# micro_amp_dual_buff.net
KiCad netlist of a schematic drawn in EAGLE
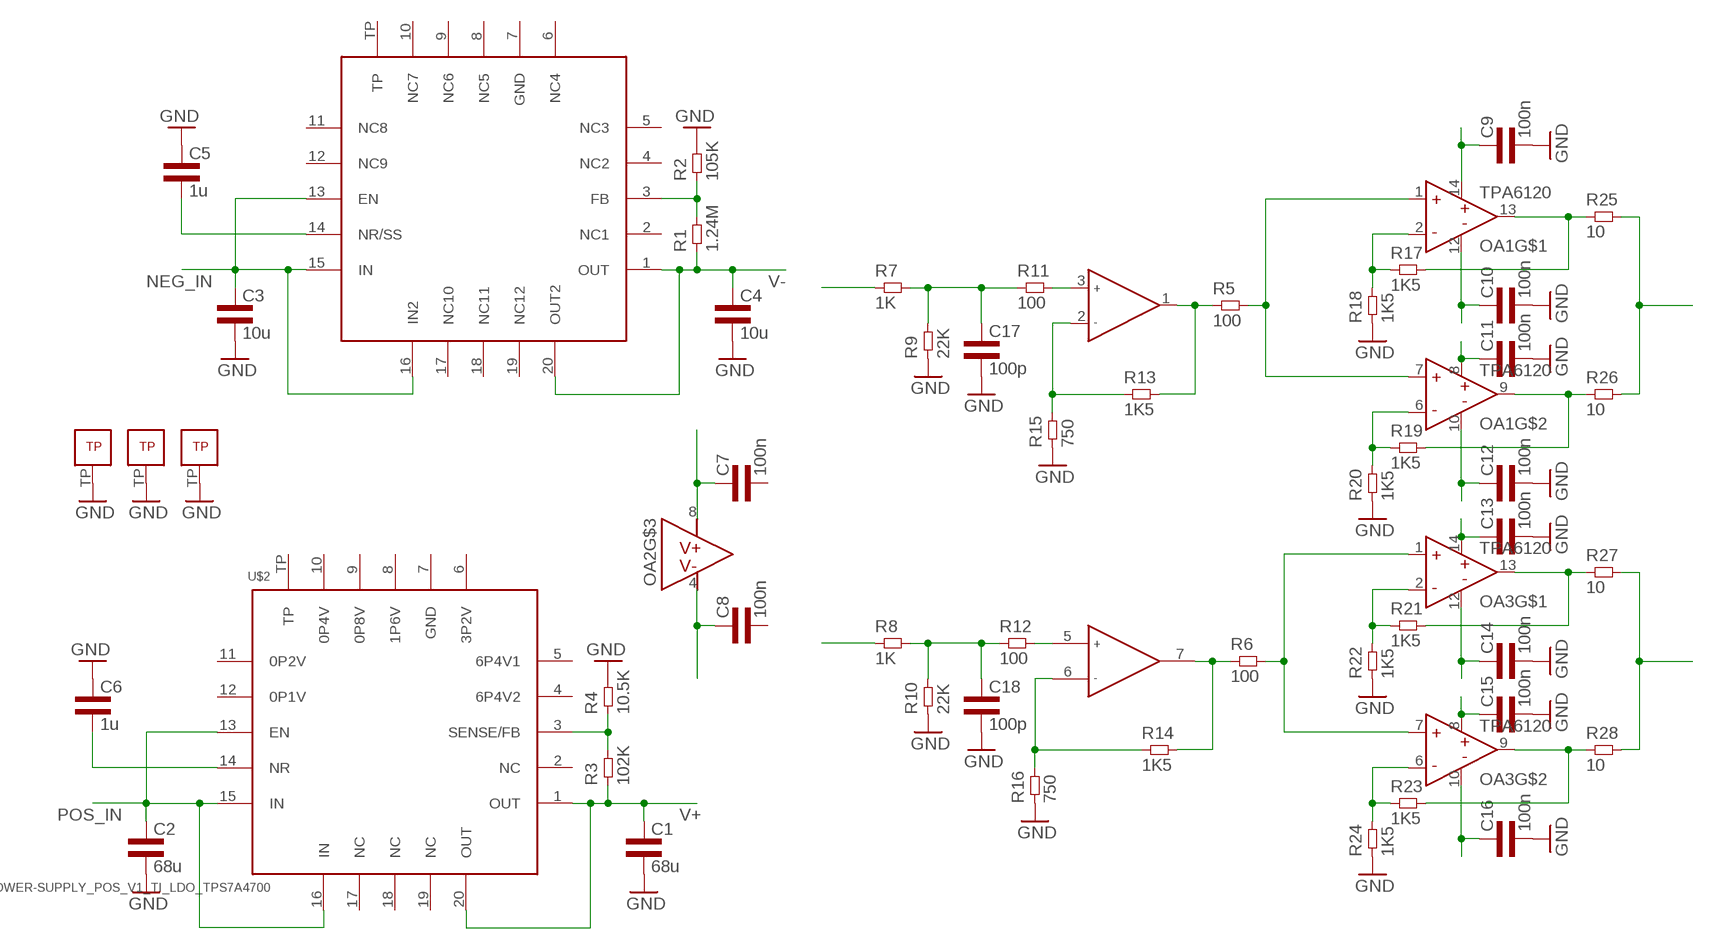
[diagram p0: schematic, sheet 1]

(export (version "E")
  (design (tool "Eeschema 10.0.6"))
  (components
    (comp (ref "C1")
      (value "68u")
      (footprint "eagle-import:1210L3")
      (libsource (lib "eagle-import") (part "CAP1210L3"))
    )
    (comp (ref "C2")
      (value "68u")
      (footprint "eagle-import:1210L3")
      (libsource (lib "eagle-import") (part "CAP1210L3"))
    )
    (comp (ref "C3")
      (value "10u")
      (footprint "eagle-import:0805L3")
      (libsource (lib "eagle-import") (part "CAP0805L3"))
    )
    (comp (ref "C4")
      (value "10u")
      (footprint "eagle-import:0805L3")
      (libsource (lib "eagle-import") (part "CAP0805L3"))
    )
    (comp (ref "C5")
      (value "1u")
      (footprint "eagle-import:0603L3")
      (libsource (lib "eagle-import") (part "CAP0603L3"))
    )
    (comp (ref "C6")
      (value "1u")
      (footprint "eagle-import:0603L3")
      (libsource (lib "eagle-import") (part "CAP0603L3"))
    )
    (comp (ref "C7")
      (value "100n")
      (footprint "eagle-import:0402L3")
      (libsource (lib "eagle-import") (part "CAP0402L3"))
    )
    (comp (ref "C8")
      (value "100n")
      (footprint "eagle-import:0402L3")
      (libsource (lib "eagle-import") (part "CAP0402L3"))
    )
    (comp (ref "C9")
      (value "100n")
      (footprint "eagle-import:0402L3")
      (libsource (lib "eagle-import") (part "CAP0402L3"))
    )
    (comp (ref "C10")
      (value "100n")
      (footprint "eagle-import:0402L3")
      (libsource (lib "eagle-import") (part "CAP0402L3"))
    )
    (comp (ref "C11")
      (value "100n")
      (footprint "eagle-import:0402L3")
      (libsource (lib "eagle-import") (part "CAP0402L3"))
    )
    (comp (ref "C12")
      (value "100n")
      (footprint "eagle-import:0402L3")
      (libsource (lib "eagle-import") (part "CAP0402L3"))
    )
    (comp (ref "C13")
      (value "100n")
      (footprint "eagle-import:0402L3")
      (libsource (lib "eagle-import") (part "CAP0402L3"))
    )
    (comp (ref "C14")
      (value "100n")
      (footprint "eagle-import:0402L3")
      (libsource (lib "eagle-import") (part "CAP0402L3"))
    )
    (comp (ref "C15")
      (value "100n")
      (footprint "eagle-import:0402L3")
      (libsource (lib "eagle-import") (part "CAP0402L3"))
    )
    (comp (ref "C16")
      (value "100n")
      (footprint "eagle-import:0402L3")
      (libsource (lib "eagle-import") (part "CAP0402L3"))
    )
    (comp (ref "C17")
      (value "100p")
      (footprint "eagle-import:0402L3")
      (libsource (lib "eagle-import") (part "CAP0402L3"))
    )
    (comp (ref "C18")
      (value "100p")
      (footprint "eagle-import:0402L3")
      (libsource (lib "eagle-import") (part "CAP0402L3"))
    )
    (comp (ref "OA1")
      (value "TPA6120QFN")
      (footprint "eagle-import:S-PVQFN-N14")
      (libsource (lib "eagle-import") (part "TPA6120QFN"))
    )
    (comp (ref "OA2")
      (value "OPA1612")
      (footprint "eagle-import:S-PWSON-N8")
      (libsource (lib "eagle-import") (part "OPA1612"))
    )
    (comp (ref "OA3")
      (value "TPA6120QFN")
      (footprint "eagle-import:S-PVQFN-N14")
      (libsource (lib "eagle-import") (part "TPA6120QFN"))
    )
    (comp (ref "R1")
      (value "1.24M")
      (footprint "eagle-import:0402L3")
      (libsource (lib "eagle-import") (part "RES0402L3"))
    )
    (comp (ref "R2")
      (value "105K")
      (footprint "eagle-import:0402L3")
      (libsource (lib "eagle-import") (part "RES0402L3"))
    )
    (comp (ref "R3")
      (value "102K")
      (footprint "eagle-import:0402L3")
      (libsource (lib "eagle-import") (part "RES0402L3"))
    )
    (comp (ref "R4")
      (value "10.5K")
      (footprint "eagle-import:0402L3")
      (libsource (lib "eagle-import") (part "RES0402L3"))
    )
    (comp (ref "R5")
      (value "100")
      (footprint "eagle-import:0402L3")
      (libsource (lib "eagle-import") (part "RES0402L3"))
    )
    (comp (ref "R6")
      (value "100")
      (footprint "eagle-import:0402L3")
      (libsource (lib "eagle-import") (part "RES0402L3"))
    )
    (comp (ref "R7")
      (value "1K")
      (footprint "eagle-import:0402L3")
      (libsource (lib "eagle-import") (part "RES0402L3"))
    )
    (comp (ref "R8")
      (value "1K")
      (footprint "eagle-import:0402L3")
      (libsource (lib "eagle-import") (part "RES0402L3"))
    )
    (comp (ref "R9")
      (value "22K")
      (footprint "eagle-import:0402L3")
      (libsource (lib "eagle-import") (part "RES0402L3"))
    )
    (comp (ref "R10")
      (value "22K")
      (footprint "eagle-import:0402L3")
      (libsource (lib "eagle-import") (part "RES0402L3"))
    )
    (comp (ref "R11")
      (value "100")
      (footprint "eagle-import:0402L3")
      (libsource (lib "eagle-import") (part "RES0402L3"))
    )
    (comp (ref "R12")
      (value "100")
      (footprint "eagle-import:0402L3")
      (libsource (lib "eagle-import") (part "RES0402L3"))
    )
    (comp (ref "R13")
      (value "1K5")
      (footprint "eagle-import:0402L3")
      (libsource (lib "eagle-import") (part "RES0402L3"))
    )
    (comp (ref "R14")
      (value "1K5")
      (footprint "eagle-import:0402L3")
      (libsource (lib "eagle-import") (part "RES0402L3"))
    )
    (comp (ref "R15")
      (value "750")
      (footprint "eagle-import:0402L3")
      (libsource (lib "eagle-import") (part "RES0402L3"))
    )
    (comp (ref "R16")
      (value "750")
      (footprint "eagle-import:0402L3")
      (libsource (lib "eagle-import") (part "RES0402L3"))
    )
    (comp (ref "R17")
      (value "1K5")
      (footprint "eagle-import:0402L3")
      (libsource (lib "eagle-import") (part "RES0402L3"))
    )
    (comp (ref "R18")
      (value "1K5")
      (footprint "eagle-import:0402L3")
      (libsource (lib "eagle-import") (part "RES0402L3"))
    )
    (comp (ref "R19")
      (value "1K5")
      (footprint "eagle-import:0402L3")
      (libsource (lib "eagle-import") (part "RES0402L3"))
    )
    (comp (ref "R20")
      (value "1K5")
      (footprint "eagle-import:0402L3")
      (libsource (lib "eagle-import") (part "RES0402L3"))
    )
    (comp (ref "R21")
      (value "1K5")
      (footprint "eagle-import:0402L3")
      (libsource (lib "eagle-import") (part "RES0402L3"))
    )
    (comp (ref "R22")
      (value "1K5")
      (footprint "eagle-import:0402L3")
      (libsource (lib "eagle-import") (part "RES0402L3"))
    )
    (comp (ref "R23")
      (value "1K5")
      (footprint "eagle-import:0402L3")
      (libsource (lib "eagle-import") (part "RES0402L3"))
    )
    (comp (ref "R24")
      (value "1K5")
      (footprint "eagle-import:0402L3")
      (libsource (lib "eagle-import") (part "RES0402L3"))
    )
    (comp (ref "R25")
      (value "10")
      (footprint "eagle-import:0805L3")
      (libsource (lib "eagle-import") (part "RES0805L3"))
    )
    (comp (ref "R26")
      (value "10")
      (footprint "eagle-import:0805L3")
      (libsource (lib "eagle-import") (part "RES0805L3"))
    )
    (comp (ref "R27")
      (value "10")
      (footprint "eagle-import:0805L3")
      (libsource (lib "eagle-import") (part "RES0805L3"))
    )
    (comp (ref "R28")
      (value "10")
      (footprint "eagle-import:0805L3")
      (libsource (lib "eagle-import") (part "RES0805L3"))
    )
    (comp (ref "U$1")
      (value "POWER-SUPPLY_POS_V1_TI_LDO_TPS7A3301RGWT")
      (footprint "eagle-import:POWER-SUPPLY_POS_V1_TI_LDO_VQFN-20")
      (libsource (lib "eagle-import") (part "POWER-SUPPLY_POS_V1_TI_LDO_TPS7A3301RGWT"))
    )
    (comp (ref "U$2")
      (value "POWER-SUPPLY_POS_V1_TI_LDO_TPS7A4700")
      (footprint "eagle-import:POWER-SUPPLY_POS_V1_TI_LDO_VQFN-20")
      (libsource (lib "eagle-import") (part "POWER-SUPPLY_POS_V1_TI_LDO_TPS7A4700"))
    )
  )
  (nets
    (net (code "1") (name "/NEG_IN") (class "Default")
      (node (ref "C3") (pin "1") (pinfunction "1_1") (pintype "bidirectional"))
      (node (ref "U$1") (pin "13") (pinfunction "EN_13") (pintype "bidirectional"))
      (node (ref "U$1") (pin "15") (pinfunction "IN_15") (pintype "bidirectional"))
      (node (ref "U$1") (pin "16") (pinfunction "IN2_16") (pintype "bidirectional"))
    )
    (net (code "2") (name "/POS_IN") (class "Default")
      (node (ref "C2") (pin "P$1") (pinfunction "1_P$1") (pintype "bidirectional"))
      (node (ref "U$2") (pin "13") (pinfunction "EN_13") (pintype "bidirectional"))
      (node (ref "U$2") (pin "15") (pinfunction "IN_15") (pintype "bidirectional"))
      (node (ref "U$2") (pin "16") (pinfunction "IN_16") (pintype "bidirectional"))
    )
    (net (code "3") (name "/V+") (class "Default")
      (node (ref "C1") (pin "P$1") (pinfunction "1_P$1") (pintype "bidirectional"))
      (node (ref "C11") (pin "P$1") (pinfunction "1_P$1") (pintype "bidirectional"))
      (node (ref "C13") (pin "P$1") (pinfunction "1_P$1") (pintype "bidirectional"))
      (node (ref "C15") (pin "P$1") (pinfunction "1_P$1") (pintype "bidirectional"))
      (node (ref "C7") (pin "P$1") (pinfunction "1_P$1") (pintype "bidirectional"))
      (node (ref "C9") (pin "P$1") (pinfunction "1_P$1") (pintype "bidirectional"))
      (node (ref "OA1") (pin "14") (pinfunction "V+_14") (pintype "bidirectional"))
      (node (ref "OA1") (pin "8") (pinfunction "V+_8") (pintype "bidirectional"))
      (node (ref "OA2") (pin "8") (pinfunction "V+_8") (pintype "power_in"))
      (node (ref "OA3") (pin "14") (pinfunction "V+_14") (pintype "bidirectional"))
      (node (ref "OA3") (pin "8") (pinfunction "V+_8") (pintype "bidirectional"))
      (node (ref "R3") (pin "P$1") (pinfunction "1_P$1") (pintype "bidirectional"))
      (node (ref "U$2") (pin "1") (pinfunction "OUT_1") (pintype "bidirectional"))
      (node (ref "U$2") (pin "20") (pinfunction "OUT_20") (pintype "bidirectional"))
    )
    (net (code "4") (name "/V-") (class "Default")
      (node (ref "C10") (pin "P$1") (pinfunction "1_P$1") (pintype "bidirectional"))
      (node (ref "C12") (pin "P$1") (pinfunction "1_P$1") (pintype "bidirectional"))
      (node (ref "C14") (pin "P$1") (pinfunction "1_P$1") (pintype "bidirectional"))
      (node (ref "C16") (pin "P$1") (pinfunction "1_P$1") (pintype "bidirectional"))
      (node (ref "C4") (pin "1") (pinfunction "1_1") (pintype "bidirectional"))
      (node (ref "C8") (pin "P$1") (pinfunction "1_P$1") (pintype "bidirectional"))
      (node (ref "OA1") (pin "10") (pinfunction "V-_10") (pintype "bidirectional"))
      (node (ref "OA1") (pin "12") (pinfunction "V-_12") (pintype "bidirectional"))
      (node (ref "OA2") (pin "4") (pinfunction "V-_4") (pintype "power_in"))
      (node (ref "OA3") (pin "10") (pinfunction "V-_10") (pintype "bidirectional"))
      (node (ref "OA3") (pin "12") (pinfunction "V-_12") (pintype "bidirectional"))
      (node (ref "R1") (pin "P$1") (pinfunction "1_P$1") (pintype "bidirectional"))
      (node (ref "U$1") (pin "1") (pinfunction "OUT_1") (pintype "bidirectional"))
      (node (ref "U$1") (pin "20") (pinfunction "OUT2_20") (pintype "bidirectional"))
    )
    (net (code "5") (name "GND") (class "Default")
      (node (ref "C1") (pin "P$2") (pinfunction "2_P$2") (pintype "bidirectional"))
      (node (ref "C10") (pin "P$2") (pinfunction "2_P$2") (pintype "bidirectional"))
      (node (ref "C11") (pin "P$2") (pinfunction "2_P$2") (pintype "bidirectional"))
      (node (ref "C12") (pin "P$2") (pinfunction "2_P$2") (pintype "bidirectional"))
      (node (ref "C13") (pin "P$2") (pinfunction "2_P$2") (pintype "bidirectional"))
      (node (ref "C14") (pin "P$2") (pinfunction "2_P$2") (pintype "bidirectional"))
      (node (ref "C15") (pin "P$2") (pinfunction "2_P$2") (pintype "bidirectional"))
      (node (ref "C16") (pin "P$2") (pinfunction "2_P$2") (pintype "bidirectional"))
      (node (ref "C17") (pin "P$2") (pinfunction "2_P$2") (pintype "bidirectional"))
      (node (ref "C18") (pin "P$2") (pinfunction "2_P$2") (pintype "bidirectional"))
      (node (ref "C2") (pin "P$2") (pinfunction "2_P$2") (pintype "bidirectional"))
      (node (ref "C3") (pin "2") (pinfunction "2_2") (pintype "bidirectional"))
      (node (ref "C4") (pin "2") (pinfunction "2_2") (pintype "bidirectional"))
      (node (ref "C5") (pin "P$1") (pinfunction "1_P$1") (pintype "bidirectional"))
      (node (ref "C6") (pin "P$1") (pinfunction "1_P$1") (pintype "bidirectional"))
      (node (ref "C9") (pin "P$2") (pinfunction "2_P$2") (pintype "bidirectional"))
      (node (ref "OA1") (pin "TP") (pinfunction "TP_TP") (pintype "bidirectional"))
      (node (ref "OA2") (pin "TP") (pinfunction "TP_TP") (pintype "bidirectional"))
      (node (ref "OA3") (pin "TP") (pinfunction "TP_TP") (pintype "bidirectional"))
      (node (ref "R10") (pin "P$1") (pinfunction "1_P$1") (pintype "bidirectional"))
      (node (ref "R15") (pin "P$1") (pinfunction "1_P$1") (pintype "bidirectional"))
      (node (ref "R16") (pin "P$1") (pinfunction "1_P$1") (pintype "bidirectional"))
      (node (ref "R18") (pin "P$1") (pinfunction "1_P$1") (pintype "bidirectional"))
      (node (ref "R2") (pin "P$2") (pinfunction "2_P$2") (pintype "bidirectional"))
      (node (ref "R20") (pin "P$1") (pinfunction "1_P$1") (pintype "bidirectional"))
      (node (ref "R22") (pin "P$1") (pinfunction "1_P$1") (pintype "bidirectional"))
      (node (ref "R24") (pin "P$1") (pinfunction "1_P$1") (pintype "bidirectional"))
      (node (ref "R4") (pin "P$2") (pinfunction "2_P$2") (pintype "bidirectional"))
      (node (ref "R9") (pin "P$1") (pinfunction "1_P$1") (pintype "bidirectional"))
    )
    (net (code "6") (name "Net-(C5-2)") (class "Default")
      (node (ref "C5") (pin "P$2") (pinfunction "2_P$2") (pintype "bidirectional"))
      (node (ref "U$1") (pin "14") (pinfunction "NR/SS_14") (pintype "bidirectional"))
    )
    (net (code "7") (name "Net-(C6-2)") (class "Default")
      (node (ref "C6") (pin "P$2") (pinfunction "2_P$2") (pintype "bidirectional"))
      (node (ref "U$2") (pin "14") (pinfunction "NR_14") (pintype "bidirectional"))
    )
    (net (code "8") (name "Net-(C17-1)") (class "Default")
      (node (ref "C17") (pin "P$1") (pinfunction "1_P$1") (pintype "bidirectional"))
      (node (ref "R11") (pin "P$1") (pinfunction "1_P$1") (pintype "bidirectional"))
      (node (ref "R7") (pin "P$2") (pinfunction "2_P$2") (pintype "bidirectional"))
      (node (ref "R9") (pin "P$2") (pinfunction "2_P$2") (pintype "bidirectional"))
    )
    (net (code "9") (name "Net-(C18-1)") (class "Default")
      (node (ref "C18") (pin "P$1") (pinfunction "1_P$1") (pintype "bidirectional"))
      (node (ref "R10") (pin "P$2") (pinfunction "2_P$2") (pintype "bidirectional"))
      (node (ref "R12") (pin "P$1") (pinfunction "1_P$1") (pintype "bidirectional"))
      (node (ref "R8") (pin "P$2") (pinfunction "2_P$2") (pintype "bidirectional"))
    )
    (net (code "10") (name "Net-(OA1A-IN+)") (class "Default")
      (node (ref "OA1") (pin "1") (pinfunction "IN+_1") (pintype "bidirectional"))
      (node (ref "OA1") (pin "7") (pinfunction "IN+_7") (pintype "bidirectional"))
      (node (ref "R5") (pin "P$2") (pinfunction "2_P$2") (pintype "bidirectional"))
    )
    (net (code "11") (name "Net-(OA1A-IN-)") (class "Default")
      (node (ref "OA1") (pin "2") (pinfunction "IN-_2") (pintype "bidirectional"))
      (node (ref "R17") (pin "P$1") (pinfunction "1_P$1") (pintype "bidirectional"))
      (node (ref "R18") (pin "P$2") (pinfunction "2_P$2") (pintype "bidirectional"))
    )
    (net (code "12") (name "Net-(OA1A-OUT)") (class "Default")
      (node (ref "OA1") (pin "13") (pinfunction "OUT_13") (pintype "bidirectional"))
      (node (ref "R17") (pin "P$2") (pinfunction "2_P$2") (pintype "bidirectional"))
      (node (ref "R25") (pin "1") (pinfunction "1_1") (pintype "bidirectional"))
    )
    (net (code "13") (name "Net-(OA1B-IN-)") (class "Default")
      (node (ref "OA1") (pin "6") (pinfunction "IN-_6") (pintype "bidirectional"))
      (node (ref "R19") (pin "P$1") (pinfunction "1_P$1") (pintype "bidirectional"))
      (node (ref "R20") (pin "P$2") (pinfunction "2_P$2") (pintype "bidirectional"))
    )
    (net (code "14") (name "Net-(OA1B-OUT)") (class "Default")
      (node (ref "OA1") (pin "9") (pinfunction "OUT_9") (pintype "bidirectional"))
      (node (ref "R19") (pin "P$2") (pinfunction "2_P$2") (pintype "bidirectional"))
      (node (ref "R26") (pin "1") (pinfunction "1_1") (pintype "bidirectional"))
    )
    (net (code "15") (name "Net-(OA2A-INA+)") (class "Default")
      (node (ref "OA2") (pin "3") (pinfunction "INA+_3") (pintype "bidirectional"))
      (node (ref "R11") (pin "P$2") (pinfunction "2_P$2") (pintype "bidirectional"))
    )
    (net (code "16") (name "Net-(OA2A-INA-)") (class "Default")
      (node (ref "OA2") (pin "2") (pinfunction "INA-_2") (pintype "bidirectional"))
      (node (ref "R13") (pin "P$1") (pinfunction "1_P$1") (pintype "bidirectional"))
      (node (ref "R15") (pin "P$2") (pinfunction "2_P$2") (pintype "bidirectional"))
    )
    (net (code "17") (name "Net-(OA2A-OUTA)") (class "Default")
      (node (ref "OA2") (pin "1") (pinfunction "OUTA_1") (pintype "bidirectional"))
      (node (ref "R13") (pin "P$2") (pinfunction "2_P$2") (pintype "bidirectional"))
      (node (ref "R5") (pin "P$1") (pinfunction "1_P$1") (pintype "bidirectional"))
    )
    (net (code "18") (name "Net-(OA2B-INB+)") (class "Default")
      (node (ref "OA2") (pin "5") (pinfunction "INB+_5") (pintype "bidirectional"))
      (node (ref "R12") (pin "P$2") (pinfunction "2_P$2") (pintype "bidirectional"))
    )
    (net (code "19") (name "Net-(OA2B-INB-)") (class "Default")
      (node (ref "OA2") (pin "6") (pinfunction "INB-_6") (pintype "bidirectional"))
      (node (ref "R14") (pin "P$1") (pinfunction "1_P$1") (pintype "bidirectional"))
      (node (ref "R16") (pin "P$2") (pinfunction "2_P$2") (pintype "bidirectional"))
    )
    (net (code "20") (name "Net-(OA2B-OUTB)") (class "Default")
      (node (ref "OA2") (pin "7") (pinfunction "OUTB_7") (pintype "bidirectional"))
      (node (ref "R14") (pin "P$2") (pinfunction "2_P$2") (pintype "bidirectional"))
      (node (ref "R6") (pin "P$1") (pinfunction "1_P$1") (pintype "bidirectional"))
    )
    (net (code "21") (name "Net-(OA3A-IN+)") (class "Default")
      (node (ref "OA3") (pin "1") (pinfunction "IN+_1") (pintype "bidirectional"))
      (node (ref "OA3") (pin "7") (pinfunction "IN+_7") (pintype "bidirectional"))
      (node (ref "R6") (pin "P$2") (pinfunction "2_P$2") (pintype "bidirectional"))
    )
    (net (code "22") (name "Net-(OA3A-IN-)") (class "Default")
      (node (ref "OA3") (pin "2") (pinfunction "IN-_2") (pintype "bidirectional"))
      (node (ref "R21") (pin "P$1") (pinfunction "1_P$1") (pintype "bidirectional"))
      (node (ref "R22") (pin "P$2") (pinfunction "2_P$2") (pintype "bidirectional"))
    )
    (net (code "23") (name "Net-(OA3A-OUT)") (class "Default")
      (node (ref "OA3") (pin "13") (pinfunction "OUT_13") (pintype "bidirectional"))
      (node (ref "R21") (pin "P$2") (pinfunction "2_P$2") (pintype "bidirectional"))
      (node (ref "R27") (pin "1") (pinfunction "1_1") (pintype "bidirectional"))
    )
    (net (code "24") (name "Net-(OA3B-IN-)") (class "Default")
      (node (ref "OA3") (pin "6") (pinfunction "IN-_6") (pintype "bidirectional"))
      (node (ref "R23") (pin "P$1") (pinfunction "1_P$1") (pintype "bidirectional"))
      (node (ref "R24") (pin "P$2") (pinfunction "2_P$2") (pintype "bidirectional"))
    )
    (net (code "25") (name "Net-(OA3B-OUT)") (class "Default")
      (node (ref "OA3") (pin "9") (pinfunction "OUT_9") (pintype "bidirectional"))
      (node (ref "R23") (pin "P$2") (pinfunction "2_P$2") (pintype "bidirectional"))
      (node (ref "R28") (pin "1") (pinfunction "1_1") (pintype "bidirectional"))
    )
    (net (code "26") (name "Net-(R1-2)") (class "Default")
      (node (ref "R1") (pin "P$2") (pinfunction "2_P$2") (pintype "bidirectional"))
      (node (ref "R2") (pin "P$1") (pinfunction "1_P$1") (pintype "bidirectional"))
      (node (ref "U$1") (pin "3") (pinfunction "FB_3") (pintype "bidirectional"))
    )
    (net (code "27") (name "Net-(R3-2)") (class "Default")
      (node (ref "R3") (pin "P$2") (pinfunction "2_P$2") (pintype "bidirectional"))
      (node (ref "R4") (pin "P$1") (pinfunction "1_P$1") (pintype "bidirectional"))
      (node (ref "U$2") (pin "3") (pinfunction "SENSE/FB_3") (pintype "bidirectional"))
    )
    (net (code "28") (name "Net-(R25-Pad2)") (class "Default")
      (node (ref "R25") (pin "2") (pinfunction "2_2") (pintype "bidirectional"))
      (node (ref "R26") (pin "2") (pinfunction "2_2") (pintype "bidirectional"))
    )
    (net (code "29") (name "Net-(R27-Pad2)") (class "Default")
      (node (ref "R27") (pin "2") (pinfunction "2_2") (pintype "bidirectional"))
      (node (ref "R28") (pin "2") (pinfunction "2_2") (pintype "bidirectional"))
    )
    (net (code "30") (name "unconnected-(C7-2-PadP$2)") (class "Default")
      (node (ref "C7") (pin "P$2") (pinfunction "2_P$2") (pintype "bidirectional"))
    )
    (net (code "31") (name "unconnected-(C8-2-PadP$2)") (class "Default")
      (node (ref "C8") (pin "P$2") (pinfunction "2_P$2") (pintype "bidirectional"))
    )
    (net (code "32") (name "unconnected-(R7-1-PadP$1)") (class "Default")
      (node (ref "R7") (pin "P$1") (pinfunction "1_P$1") (pintype "bidirectional"))
    )
    (net (code "33") (name "unconnected-(R8-1-PadP$1)") (class "Default")
      (node (ref "R8") (pin "P$1") (pinfunction "1_P$1") (pintype "bidirectional"))
    )
    (net (code "34") (name "unconnected-(U$1-GND-Pad7)") (class "Default")
      (node (ref "U$1") (pin "7") (pinfunction "GND_7") (pintype "bidirectional"))
    )
    (net (code "35") (name "unconnected-(U$1-NC1-Pad2)") (class "Default")
      (node (ref "U$1") (pin "2") (pinfunction "NC1_2") (pintype "bidirectional"))
    )
    (net (code "36") (name "unconnected-(U$1-NC2-Pad4)") (class "Default")
      (node (ref "U$1") (pin "4") (pinfunction "NC2_4") (pintype "bidirectional"))
    )
    (net (code "37") (name "unconnected-(U$1-NC3-Pad5)") (class "Default")
      (node (ref "U$1") (pin "5") (pinfunction "NC3_5") (pintype "bidirectional"))
    )
    (net (code "38") (name "unconnected-(U$1-NC4-Pad6)") (class "Default")
      (node (ref "U$1") (pin "6") (pinfunction "NC4_6") (pintype "bidirectional"))
    )
    (net (code "39") (name "unconnected-(U$1-NC5-Pad8)") (class "Default")
      (node (ref "U$1") (pin "8") (pinfunction "NC5_8") (pintype "bidirectional"))
    )
    (net (code "40") (name "unconnected-(U$1-NC6-Pad9)") (class "Default")
      (node (ref "U$1") (pin "9") (pinfunction "NC6_9") (pintype "bidirectional"))
    )
    (net (code "41") (name "unconnected-(U$1-NC7-Pad10)") (class "Default")
      (node (ref "U$1") (pin "10") (pinfunction "NC7_10") (pintype "bidirectional"))
    )
    (net (code "42") (name "unconnected-(U$1-NC8-Pad11)") (class "Default")
      (node (ref "U$1") (pin "11") (pinfunction "NC8_11") (pintype "bidirectional"))
    )
    (net (code "43") (name "unconnected-(U$1-NC9-Pad12)") (class "Default")
      (node (ref "U$1") (pin "12") (pinfunction "NC9_12") (pintype "bidirectional"))
    )
    (net (code "44") (name "unconnected-(U$1-NC10-Pad17)") (class "Default")
      (node (ref "U$1") (pin "17") (pinfunction "NC10_17") (pintype "bidirectional"))
    )
    (net (code "45") (name "unconnected-(U$1-NC11-Pad18)") (class "Default")
      (node (ref "U$1") (pin "18") (pinfunction "NC11_18") (pintype "bidirectional"))
    )
    (net (code "46") (name "unconnected-(U$1-NC12-Pad19)") (class "Default")
      (node (ref "U$1") (pin "19") (pinfunction "NC12_19") (pintype "bidirectional"))
    )
    (net (code "47") (name "unconnected-(U$1-PadTP)") (class "Default")
      (node (ref "U$1") (pin "TP") (pinfunction "TP_TP") (pintype "bidirectional"))
    )
    (net (code "48") (name "unconnected-(U$2-0P1V-Pad12)") (class "Default")
      (node (ref "U$2") (pin "12") (pinfunction "0P1V_12") (pintype "bidirectional"))
    )
    (net (code "49") (name "unconnected-(U$2-0P2V-Pad11)") (class "Default")
      (node (ref "U$2") (pin "11") (pinfunction "0P2V_11") (pintype "bidirectional"))
    )
    (net (code "50") (name "unconnected-(U$2-0P4V-Pad10)") (class "Default")
      (node (ref "U$2") (pin "10") (pinfunction "0P4V_10") (pintype "bidirectional"))
    )
    (net (code "51") (name "unconnected-(U$2-0P8V-Pad9)") (class "Default")
      (node (ref "U$2") (pin "9") (pinfunction "0P8V_9") (pintype "bidirectional"))
    )
    (net (code "52") (name "unconnected-(U$2-1P6V-Pad8)") (class "Default")
      (node (ref "U$2") (pin "8") (pinfunction "1P6V_8") (pintype "bidirectional"))
    )
    (net (code "53") (name "unconnected-(U$2-3P2V-Pad6)") (class "Default")
      (node (ref "U$2") (pin "6") (pinfunction "3P2V_6") (pintype "bidirectional"))
    )
    (net (code "54") (name "unconnected-(U$2-6P4V1-Pad5)") (class "Default")
      (node (ref "U$2") (pin "5") (pinfunction "6P4V1_5") (pintype "bidirectional"))
    )
    (net (code "55") (name "unconnected-(U$2-6P4V2-Pad4)") (class "Default")
      (node (ref "U$2") (pin "4") (pinfunction "6P4V2_4") (pintype "bidirectional"))
    )
    (net (code "56") (name "unconnected-(U$2-GND-Pad7)") (class "Default")
      (node (ref "U$2") (pin "7") (pinfunction "GND_7") (pintype "bidirectional"))
    )
    (net (code "57") (name "unconnected-(U$2-NC-Pad2)") (class "Default")
      (node (ref "U$2") (pin "2") (pinfunction "NC_2") (pintype "bidirectional"))
    )
    (net (code "58") (name "unconnected-(U$2-NC-Pad17)") (class "Default")
      (node (ref "U$2") (pin "17") (pinfunction "NC_17") (pintype "bidirectional"))
    )
    (net (code "59") (name "unconnected-(U$2-NC-Pad18)") (class "Default")
      (node (ref "U$2") (pin "18") (pinfunction "NC_18") (pintype "bidirectional"))
    )
    (net (code "60") (name "unconnected-(U$2-NC-Pad19)") (class "Default")
      (node (ref "U$2") (pin "19") (pinfunction "NC_19") (pintype "bidirectional"))
    )
    (net (code "61") (name "unconnected-(U$2-PadTP)") (class "Default")
      (node (ref "U$2") (pin "TP") (pinfunction "TP_TP") (pintype "bidirectional"))
    )
  )
)
